# 03-Power_3v3.net
KiCad netlist of a schematic drawn in Altium Designer
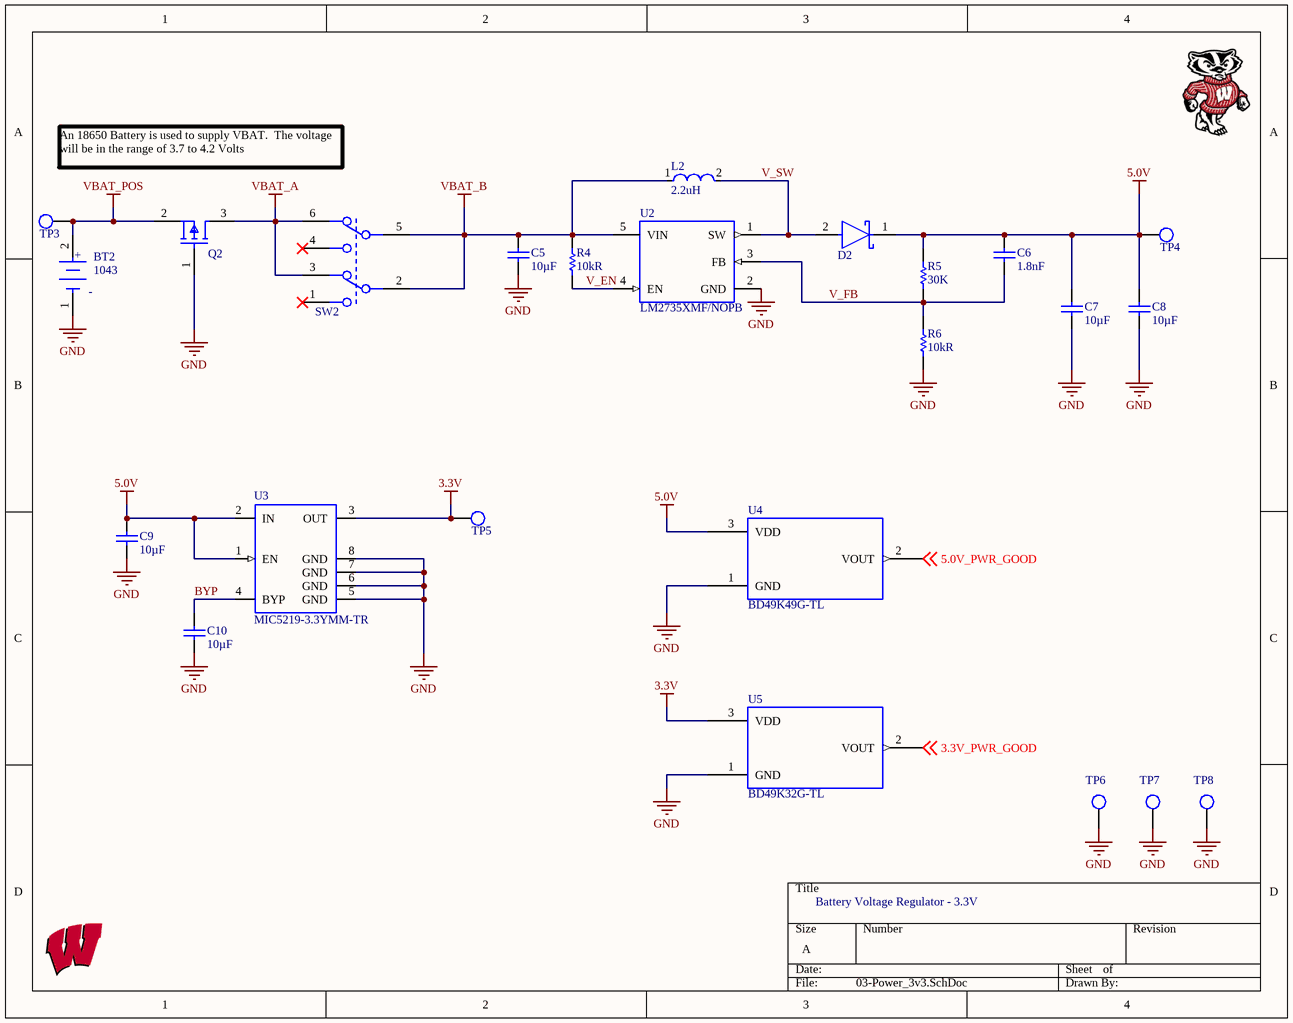
[diagram p0: 03-Power_3v3.SchDoc]

(export (version "E")
  (design (tool "Eeschema 10.0.6"))
  (components
    (comp (ref "BT2")
      (value "1043")
      (footprint "Keystone_1043_0")
      (description "Cylindrical Battery Contacts, Clips, Holders & Springs 18650 PCB PLASTIC BATT HLDR THM 1 CELL")
      (fields (field (name "MANUFACTURER PART NUMBER 1") "1043"))
      (libsource (lib "Battery") (part "1043"))
    )
    (comp (ref "C5")
      (value "10µF")
      (footprint "CAP_0805")
      (description "CAP CER 10UF 10V X5R 0805")
      (fields
        (field (name "MANUFACTURER") "Samsung Electro-Mechanics America, Inc.")
        (field (name "MANUFACTURER PART NUMBER") "CL21A106KPCLQNC")
      )
      (libsource (lib "Cap_Ceramic") (part "CAP_0805_U_010_00"))
    )
    (comp (ref "C6")
      (value "CAP_0805_N_001_80")
      (footprint "CAP_0805")
      (fields
        (field (name "TOLERANCE") "5%")
        (field (name "VOLTAGE") "50V")
        (field (name "CAPACITANCE") "1.8nF")
      )
      (libsource (lib "Cap_Ceramic") (part "CAP_0805_N_001_80"))
    )
    (comp (ref "C7")
      (value "10µF")
      (footprint "CAP_0805")
      (description "CAP CER 10UF 10V X5R 0805")
      (fields
        (field (name "MANUFACTURER") "Samsung Electro-Mechanics America, Inc.")
        (field (name "MANUFACTURER PART NUMBER") "CL21A106KPCLQNC")
      )
      (libsource (lib "Cap_Ceramic") (part "CAP_0805_U_010_00"))
    )
    (comp (ref "C8")
      (value "10µF")
      (footprint "CAP_0805")
      (description "CAP CER 10UF 10V X5R 0805")
      (fields
        (field (name "MANUFACTURER") "Samsung Electro-Mechanics America, Inc.")
        (field (name "MANUFACTURER PART NUMBER") "CL21A106KPCLQNC")
      )
      (libsource (lib "Cap_Ceramic") (part "CAP_0805_U_010_00"))
    )
    (comp (ref "C9")
      (value "10µF")
      (footprint "CAP_0805")
      (description "CAP CER 10UF 10V X5R 0805")
      (fields
        (field (name "MANUFACTURER") "Samsung Electro-Mechanics America, Inc.")
        (field (name "MANUFACTURER PART NUMBER") "CL21A106KPCLQNC")
      )
      (libsource (lib "Cap_Ceramic") (part "CAP_0805_U_010_00"))
    )
    (comp (ref "C10")
      (value "10µF")
      (footprint "CAP_0805")
      (description "CAP CER 10UF 10V X5R 0805")
      (fields
        (field (name "MANUFACTURER") "Samsung Electro-Mechanics America, Inc.")
        (field (name "MANUFACTURER PART NUMBER") "CL21A106KPCLQNC")
      )
      (libsource (lib "Cap_Ceramic") (part "CAP_0805_U_010_00"))
    )
    (comp (ref "D2")
      (value "SM5817PL-TP")
      (footprint "On_Semiconductor_425-04_IPC_A")
      (description "DIODE SCHOTTKY 20V 1A SOD123FL")
      (libsource (lib "Diodes") (part "SM5817PL-TP"))
    )
    (comp (ref "L2")
      (value "NRS4018T2R2MDGJ")
      (footprint "IND_TAIYO_NRS4018_TAY")
      (description "Inductor Power Shielded Wirewound 2.2uH 20% 100KHz Ferrite 2.2A 0.0504Ohm DCR 1515 T/R")
      (fields (field (name "TOLERANCE") "20%") (field (name "INDUCTANCE") "2.2uH"))
      (libsource (lib "Inductors") (part "NRS4018T2R2MDGJ"))
    )
    (comp (ref "Q2")
      (value "SSM3J328R,LF")
      (footprint "SOT-23_M")
      (description "MOSFET P-CH 20V 6A SOT23F")
      (libsource (lib "Transistors") (part "SSM3J328R,LF"))
    )
    (comp (ref "R4")
      (value "RES_0805_K_010.00")
      (footprint "RES_0805")
      (description "RES SMD 10K OHM 1% 1/8W 0805")
      (fields (field (name "TOLERANCE") "1%") (field (name "RESISTANCE") "10kR"))
      (libsource (lib "Resistors") (part "RES_0805_K_010.00"))
    )
    (comp (ref "R5")
      (value "30K")
      (footprint "RES_0805")
      (description "Res Thick Film 0805 30K Ohm 1% 0.125W(1/8W) ±100ppm/°C Pad SMD Automotive T/R")
      (fields (field (name "TOLERANCE") "1%") (field (name "RESISTANCE") "30K"))
      (libsource (lib "Resistors") (part "RES_0805_K_030.00"))
    )
    (comp (ref "R6")
      (value "RES_0805_K_010.00")
      (footprint "RES_0805")
      (description "RES SMD 10K OHM 1% 1/8W 0805")
      (fields (field (name "TOLERANCE") "1%") (field (name "RESISTANCE") "10kR"))
      (libsource (lib "Resistors") (part "RES_0805_K_010.00"))
    )
    (comp (ref "SW2")
      (value "JS202011SCQN")
      (footprint "C&K_Components_0_MFG")
      (description "C & K COMPONENTS - JS202011SCQN - SWITCH, DPDT, 0.6A, 6VDC, SMD")
      (libsource (lib "Switches") (part "JS202011SCQN"))
    )
    (comp (ref "TP3")
      (value "TP_1206")
      (footprint "TP-SMC-1206")
      (description "Test Point SMD 1206")
      (fields
        (field (name "MANUFACTURER") "TE Connectivity (Tyco Electronics)")
        (field (name "MANUFACTURER PART NUMBER") "1625854-1")
      )
      (libsource (lib "Mechanical") (part "TP_1206"))
    )
    (comp (ref "TP4")
      (value "TP_1206")
      (footprint "TP-SMC-1206")
      (description "Test Point SMD 1206")
      (fields
        (field (name "MANUFACTURER") "TE Connectivity (Tyco Electronics)")
        (field (name "MANUFACTURER PART NUMBER") "1625854-1")
      )
      (libsource (lib "Mechanical") (part "TP_1206"))
    )
    (comp (ref "TP5")
      (value "TP_1206")
      (footprint "TP-SMC-1206")
      (description "Test Point SMD 1206")
      (fields
        (field (name "MANUFACTURER") "TE Connectivity (Tyco Electronics)")
        (field (name "MANUFACTURER PART NUMBER") "1625854-1")
      )
      (libsource (lib "Mechanical") (part "TP_1206"))
    )
    (comp (ref "TP6")
      (value "TP_1206")
      (footprint "TP-SMC-1206")
      (description "Test Point SMD 1206")
      (fields
        (field (name "MANUFACTURER") "TE Connectivity (Tyco Electronics)")
        (field (name "MANUFACTURER PART NUMBER") "1625854-1")
      )
      (libsource (lib "Mechanical") (part "TP_1206"))
    )
    (comp (ref "TP7")
      (value "TP_1206")
      (footprint "TP-SMC-1206")
      (description "Test Point SMD 1206")
      (fields
        (field (name "MANUFACTURER") "TE Connectivity (Tyco Electronics)")
        (field (name "MANUFACTURER PART NUMBER") "1625854-1")
      )
      (libsource (lib "Mechanical") (part "TP_1206"))
    )
    (comp (ref "TP8")
      (value "TP_1206")
      (footprint "TP-SMC-1206")
      (description "Test Point SMD 1206")
      (fields
        (field (name "MANUFACTURER") "TE Connectivity (Tyco Electronics)")
        (field (name "MANUFACTURER PART NUMBER") "1625854-1")
      )
      (libsource (lib "Mechanical") (part "TP_1206"))
    )
    (comp (ref "U2")
      (value "LM2735XMF-NOPB")
      (footprint "Texas_Instruments_DBV0005A_0")
      (description "IC REG MULT CONFG ADJ 2.1A SOT23")
      (fields (field (name "MANUFACTURER PART NUMBER 1") "LM2735XMF/NOPB"))
      (libsource (lib "Regulators") (part "LM2735XMF-NOPB"))
    )
    (comp (ref "U3")
      (value "MIC5219-3.3YMM-TR")
      (footprint "MIC5219-3.3YMM-TR")
      (description "MIC5219 Series 500 mA 3.3 V Fixed Output Surface Mount LDO Regulator- MSOP-8 T/R")
      (libsource (lib "Regulators") (part "MIC5219-3.3YMM-TR"))
    )
    (comp (ref "U4")
      (value "BD49K49G-TL")
      (footprint "ROHM-SSOP3_ROM-M")
      (description "Processor Supervisor 4.9V 1 Active Low/CMOS 3-Pin SSOP T/R")
      (fields (field (name "COPYRIGHT") "Copyright (C) 2022 Ultra Librarian. All rights reserved."))
      (libsource (lib "ICs") (part "BD49K49G-TL"))
    )
    (comp (ref "U5")
      (value "BD49K32G-TL")
      (footprint "ROHM-SSOP3_ROM-M")
      (description "Processor Supervisor 3.2V 1 Active Low/CMOS 3-Pin SSOP T/R")
      (libsource (lib "ICs") (part "BD49K32G-TL"))
    )
  )
  (nets
    (net (code "1") (name "/BYP") (class "Default")
      (node (ref "C10") (pin "2") (pinfunction "2_2") (pintype "passive"))
      (node (ref "U3") (pin "4") (pinfunction "BYP_4") (pintype "power_in"))
    )
    (net (code "2") (name "/V_EN") (class "Default")
      (node (ref "R4") (pin "1") (pinfunction "1_1") (pintype "passive"))
      (node (ref "U2") (pin "4") (pinfunction "EN_4") (pintype "input"))
    )
    (net (code "3") (name "/V_FB") (class "Default")
      (node (ref "C6") (pin "1") (pinfunction "1_1") (pintype "passive"))
      (node (ref "R5") (pin "1") (pinfunction "1_1") (pintype "passive"))
      (node (ref "R6") (pin "2") (pinfunction "2_2") (pintype "passive"))
      (node (ref "U2") (pin "3") (pinfunction "FB_3") (pintype "input"))
    )
    (net (code "4") (name "/V_SW") (class "Default")
      (node (ref "D2") (pin "2") (pinfunction "A_2") (pintype "passive"))
      (node (ref "L2") (pin "2") (pinfunction "2_2") (pintype "passive"))
      (node (ref "U2") (pin "1") (pinfunction "SW_1") (pintype "output"))
    )
    (net (code "5") (name "3.3V") (class "Default")
      (node (ref "TP5") (pin "1") (pintype "passive"))
      (node (ref "U3") (pin "3") (pinfunction "OUT_3") (pintype "power_in"))
      (node (ref "U5") (pin "3") (pinfunction "VDD_3") (pintype "power_in"))
    )
    (net (code "6") (name "3.3V_PWR_GOOD") (class "Default")
      (node (ref "U5") (pin "2") (pinfunction "VOUT_2") (pintype "output"))
    )
    (net (code "7") (name "5.0V") (class "Default")
      (node (ref "C6") (pin "2") (pinfunction "2_2") (pintype "passive"))
      (node (ref "C7") (pin "2") (pinfunction "2_2") (pintype "passive"))
      (node (ref "C8") (pin "2") (pinfunction "2_2") (pintype "passive"))
      (node (ref "C9") (pin "2") (pinfunction "2_2") (pintype "passive"))
      (node (ref "D2") (pin "1") (pinfunction "C_1") (pintype "passive"))
      (node (ref "R5") (pin "2") (pinfunction "2_2") (pintype "passive"))
      (node (ref "TP4") (pin "1") (pintype "passive"))
      (node (ref "U3") (pin "1") (pinfunction "EN_1") (pintype "input"))
      (node (ref "U3") (pin "2") (pinfunction "IN_2") (pintype "power_in"))
      (node (ref "U4") (pin "3") (pinfunction "VDD_3") (pintype "power_in"))
    )
    (net (code "8") (name "5.0V_PWR_GOOD") (class "Default")
      (node (ref "U4") (pin "2") (pinfunction "VOUT_2") (pintype "output"))
    )
    (net (code "9") (name "GND") (class "Default")
      (node (ref "BT2") (pin "1") (pinfunction "C_1") (pintype "passive"))
      (node (ref "C10") (pin "1") (pinfunction "1_1") (pintype "passive"))
      (node (ref "C5") (pin "1") (pinfunction "1_1") (pintype "passive"))
      (node (ref "C7") (pin "1") (pinfunction "1_1") (pintype "passive"))
      (node (ref "C8") (pin "1") (pinfunction "1_1") (pintype "passive"))
      (node (ref "C9") (pin "1") (pinfunction "1_1") (pintype "passive"))
      (node (ref "Q2") (pin "1") (pinfunction "Gate_1") (pintype "passive"))
      (node (ref "R6") (pin "1") (pinfunction "1_1") (pintype "passive"))
      (node (ref "TP6") (pin "1") (pintype "passive"))
      (node (ref "TP7") (pin "1") (pintype "passive"))
      (node (ref "TP8") (pin "1") (pintype "passive"))
      (node (ref "U2") (pin "2") (pinfunction "GND_2") (pintype "power_in"))
      (node (ref "U3") (pin "5") (pinfunction "GND_5") (pintype "power_in"))
      (node (ref "U3") (pin "6") (pinfunction "GND_6") (pintype "power_in"))
      (node (ref "U3") (pin "7") (pinfunction "GND_7") (pintype "power_in"))
      (node (ref "U3") (pin "8") (pinfunction "GND_8") (pintype "power_in"))
      (node (ref "U4") (pin "1") (pinfunction "GND_1") (pintype "passive"))
      (node (ref "U5") (pin "1") (pinfunction "GND_1") (pintype "passive"))
    )
    (net (code "10") (name "VBAT_A") (class "Default")
      (node (ref "Q2") (pin "3") (pinfunction "Drain_3") (pintype "passive"))
      (node (ref "SW2") (pin "3") (pinfunction "3_3") (pintype "passive"))
      (node (ref "SW2") (pin "6") (pinfunction "6_6") (pintype "passive"))
    )
    (net (code "11") (name "VBAT_B") (class "Default")
      (node (ref "C5") (pin "2") (pinfunction "2_2") (pintype "passive"))
      (node (ref "L2") (pin "1") (pinfunction "1_1") (pintype "passive"))
      (node (ref "R4") (pin "2") (pinfunction "2_2") (pintype "passive"))
      (node (ref "SW2") (pin "2") (pinfunction "2_2") (pintype "passive"))
      (node (ref "SW2") (pin "5") (pinfunction "5_5") (pintype "passive"))
      (node (ref "U2") (pin "5") (pinfunction "VIN_5") (pintype "power_in"))
    )
    (net (code "12") (name "VBAT_POS") (class "Default")
      (node (ref "BT2") (pin "2") (pinfunction "A_2") (pintype "passive"))
      (node (ref "Q2") (pin "2") (pinfunction "Source_2") (pintype "passive"))
      (node (ref "TP3") (pin "1") (pintype "passive"))
    )
    (net (code "13") (name "unconnected-(SW2-Pad1)") (class "Default")
      (node (ref "SW2") (pin "1") (pinfunction "1_1") (pintype "passive+no_connect"))
    )
    (net (code "14") (name "unconnected-(SW2-Pad4)") (class "Default")
      (node (ref "SW2") (pin "4") (pinfunction "4_4") (pintype "passive+no_connect"))
    )
  )
)
